# SCH_555-Circuit_2025-03-26.net
KiCad netlist of a schematic drawn in EasyEDA
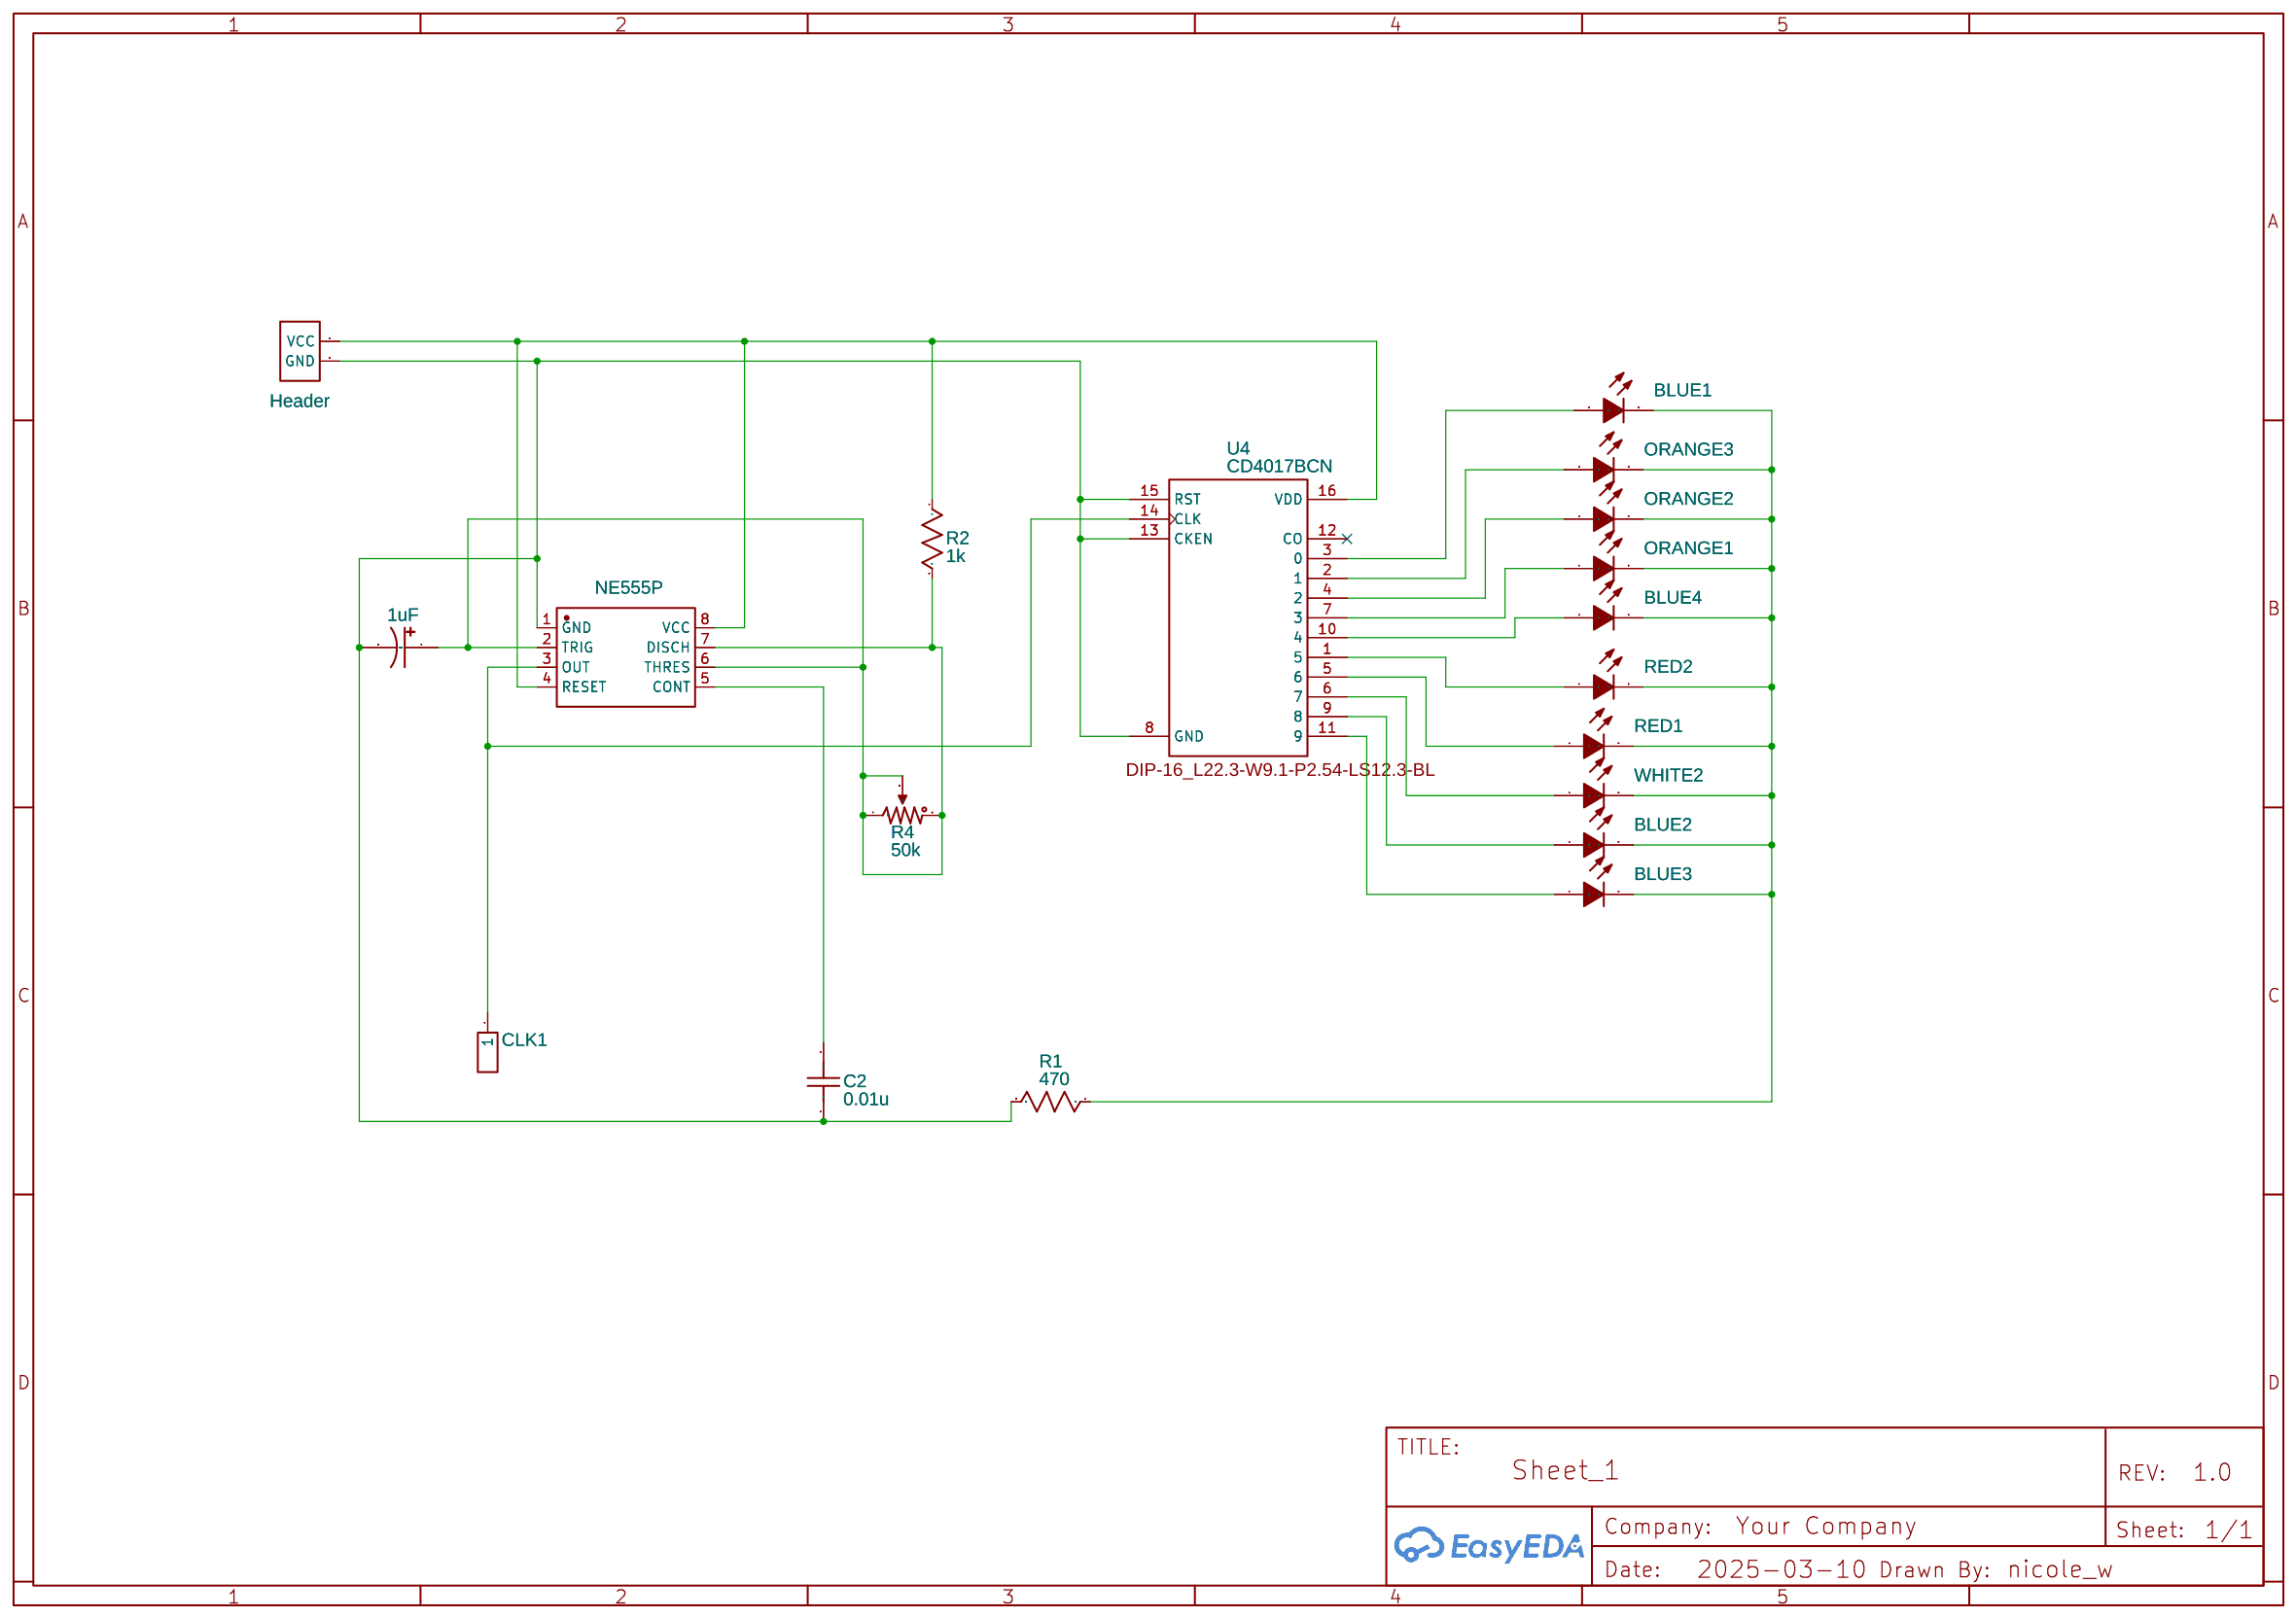
[diagram p0: schematic sheet]

(export (version "E")
  (design (tool "Eeschema 10.0.6"))
  (components
    (comp (ref "BLUE1") (value "LED_5MM") (libsource (lib "") (part "LED_5MM_2")))
    (comp (ref "BLUE2") (value "LED_5MM") (libsource (lib "") (part "LED_5MM_2")))
    (comp (ref "BLUE3") (value "LED_5MM") (libsource (lib "") (part "LED_5MM_2")))
    (comp (ref "BLUE4") (value "LED_5MM") (libsource (lib "") (part "LED_5MM_2")))
    (comp (ref "C1")
      (value "1uF")
      (fields (field (name "Manufacturer Part") "UVZ1H010MDD") (field (name "Manufacturer") "Nichicon(尼吉康)"))
      (libsource (lib "") (part "UVZ1H010MDD"))
    )
    (comp (ref "C2") (value "0.01u") (libsource (lib "") (part "C_0603_US")))
    (comp (ref "CLK1")
      (value "C81276")
      (fields
        (field (name "Manufacturer Part") "2.54-1*1P针")
        (field (name "Manufacturer") "BOOMELE(Boom Precision Elec)")
      )
      (libsource (lib "") (part "Header-Male-2.54_1x1"))
    )
    (comp (ref "H1") (value "Header") (libsource (lib "") (part "HEADER-FEMALE-2.54_1X2")))
    (comp (ref "ORANGE1") (value "LED_5MM") (libsource (lib "") (part "LED_5MM_1")))
    (comp (ref "ORANGE2") (value "LED_5MM") (libsource (lib "") (part "LED_5MM_1")))
    (comp (ref "ORANGE3") (value "LED_5MM") (libsource (lib "") (part "LED_5MM_1")))
    (comp (ref "R1")
      (value "470")
      (fields (field (name "Manufacturer Part") "?"))
      (libsource (lib "") (part "Resistor"))
    )
    (comp (ref "R2")
      (value "1k")
      (fields (field (name "Manufacturer Part") "?"))
      (libsource (lib "") (part "Resistor_1"))
    )
    (comp (ref "R4")
      (value "50k")
      (fields (field (name "Manufacturer Part") "?"))
      (libsource (lib "") (part "Potentiometer"))
    )
    (comp (ref "RED1") (value "LED_5MM") (libsource (lib "") (part "LED_5MM_3")))
    (comp (ref "RED2") (value "LED_5MM") (libsource (lib "") (part "LED_5MM_3")))
    (comp (ref "U2")
      (value "NE555P")
      (fields (field (name "Manufacturer") "TI(德州仪器)"))
      (libsource (lib "") (part "NE555P"))
    )
    (comp (ref "U4") (value "CD4017BCN") (libsource (lib "") (part "CD4017BCN")))
    (comp (ref "WHITE2") (value "LED_5MM") (libsource (lib "") (part "LED_5MM")))
  )
  (nets
    (net (code "1") (name "Net-(BLUE1-A)") (class "Default")
      (node (ref "BLUE1") (pin "1") (pinfunction "A_1") (pintype "input"))
      (node (ref "U4") (pin "3") (pinfunction "0_3") (pintype "output"))
    )
    (net (code "2") (name "Net-(BLUE1-K)") (class "Default")
      (node (ref "BLUE1") (pin "2") (pinfunction "K_2") (pintype "input"))
      (node (ref "BLUE2") (pin "2") (pinfunction "K_2") (pintype "input"))
      (node (ref "BLUE3") (pin "2") (pinfunction "K_2") (pintype "input"))
      (node (ref "BLUE4") (pin "2") (pinfunction "K_2") (pintype "input"))
      (node (ref "ORANGE1") (pin "2") (pinfunction "K_2") (pintype "input"))
      (node (ref "ORANGE2") (pin "2") (pinfunction "K_2") (pintype "input"))
      (node (ref "ORANGE3") (pin "2") (pinfunction "K_2") (pintype "input"))
      (node (ref "R1") (pin "1") (pinfunction "1_1") (pintype "unspecified"))
      (node (ref "RED1") (pin "2") (pinfunction "K_2") (pintype "input"))
      (node (ref "RED2") (pin "2") (pinfunction "K_2") (pintype "input"))
      (node (ref "WHITE2") (pin "2") (pinfunction "K_2") (pintype "input"))
    )
    (net (code "3") (name "Net-(BLUE2-A)") (class "Default")
      (node (ref "BLUE2") (pin "1") (pinfunction "A_1") (pintype "input"))
      (node (ref "U4") (pin "9") (pinfunction "8_9") (pintype "output"))
    )
    (net (code "4") (name "Net-(BLUE3-A)") (class "Default")
      (node (ref "BLUE3") (pin "1") (pinfunction "A_1") (pintype "input"))
      (node (ref "U4") (pin "11") (pinfunction "9_11") (pintype "output"))
    )
    (net (code "5") (name "Net-(BLUE4-A)") (class "Default")
      (node (ref "BLUE4") (pin "1") (pinfunction "A_1") (pintype "input"))
      (node (ref "U4") (pin "10") (pinfunction "4_10") (pintype "output"))
    )
    (net (code "6") (name "Net-(H1-GND)") (class "Default")
      (node (ref "C1") (pin "2") (pinfunction "2_2") (pintype "unspecified"))
      (node (ref "C2") (pin "1") (pinfunction "1_1") (pintype "unspecified"))
      (node (ref "H1") (pin "2") (pinfunction "GND_2") (pintype "unspecified"))
      (node (ref "R1") (pin "2") (pinfunction "2_2") (pintype "unspecified"))
      (node (ref "U2") (pin "1") (pinfunction "GND_1") (pintype "unspecified"))
      (node (ref "U4") (pin "13") (pinfunction "CKEN_13") (pintype "unspecified"))
      (node (ref "U4") (pin "15") (pinfunction "RST_15") (pintype "unspecified"))
      (node (ref "U4") (pin "8") (pinfunction "GND_8") (pintype "passive"))
    )
    (net (code "7") (name "Net-(H1-VCC)") (class "Default")
      (node (ref "H1") (pin "1") (pinfunction "VCC_1") (pintype "unspecified"))
      (node (ref "R2") (pin "1") (pinfunction "1_1") (pintype "unspecified"))
      (node (ref "U2") (pin "4") (pinfunction "RESET_4") (pintype "unspecified"))
      (node (ref "U2") (pin "8") (pinfunction "VCC_8") (pintype "unspecified"))
      (node (ref "U4") (pin "16") (pinfunction "VDD_16") (pintype "passive"))
    )
    (net (code "8") (name "Net-(ORANGE1-A)") (class "Default")
      (node (ref "ORANGE1") (pin "1") (pinfunction "A_1") (pintype "input"))
      (node (ref "U4") (pin "7") (pinfunction "3_7") (pintype "output"))
    )
    (net (code "9") (name "Net-(ORANGE2-A)") (class "Default")
      (node (ref "ORANGE2") (pin "1") (pinfunction "A_1") (pintype "input"))
      (node (ref "U4") (pin "4") (pinfunction "2_4") (pintype "output"))
    )
    (net (code "10") (name "Net-(ORANGE3-A)") (class "Default")
      (node (ref "ORANGE3") (pin "1") (pinfunction "A_1") (pintype "input"))
      (node (ref "U4") (pin "2") (pinfunction "1_2") (pintype "output"))
    )
    (net (code "11") (name "Net-(R4-2)") (class "Default")
      (node (ref "C1") (pin "1") (pinfunction "1_1") (pintype "unspecified"))
      (node (ref "R2") (pin "2") (pinfunction "2_2") (pintype "unspecified"))
      (node (ref "R4") (pin "1") (pinfunction "1_1") (pintype "unspecified"))
      (node (ref "R4") (pin "2") (pinfunction "3_2") (pintype "unspecified"))
      (node (ref "R4") (pin "3") (pinfunction "2_3") (pintype "unspecified"))
      (node (ref "U2") (pin "2") (pinfunction "TRIG_2") (pintype "unspecified"))
      (node (ref "U2") (pin "6") (pinfunction "THRES_6") (pintype "unspecified"))
      (node (ref "U2") (pin "7") (pinfunction "DISCH_7") (pintype "unspecified"))
    )
    (net (code "12") (name "Net-(RED1-A)") (class "Default")
      (node (ref "RED1") (pin "1") (pinfunction "A_1") (pintype "input"))
      (node (ref "U4") (pin "5") (pinfunction "6_5") (pintype "output"))
    )
    (net (code "13") (name "Net-(RED2-A)") (class "Default")
      (node (ref "RED2") (pin "1") (pinfunction "A_1") (pintype "input"))
      (node (ref "U4") (pin "1") (pinfunction "5_1") (pintype "output"))
    )
    (net (code "14") (name "Net-(U2-CONT)") (class "Default")
      (node (ref "C2") (pin "2") (pinfunction "2_2") (pintype "unspecified"))
      (node (ref "U2") (pin "5") (pinfunction "CONT_5") (pintype "unspecified"))
    )
    (net (code "15") (name "Net-(U2-OUT)") (class "Default")
      (node (ref "CLK1") (pin "1") (pinfunction "1_1") (pintype "unspecified"))
      (node (ref "U2") (pin "3") (pinfunction "OUT_3") (pintype "unspecified"))
      (node (ref "U4") (pin "14") (pinfunction "CLK_14") (pintype "unspecified"))
    )
    (net (code "16") (name "Net-(U4-7)") (class "Default")
      (node (ref "U4") (pin "6") (pinfunction "7_6") (pintype "output"))
      (node (ref "WHITE2") (pin "1") (pinfunction "A_1") (pintype "input"))
    )
    (net (code "17") (name "unconnected-(U4-CO-Pad12)") (class "Default")
      (node (ref "U4") (pin "12") (pinfunction "CO_12") (pintype "output+no_connect"))
    )
  )
)
